# CAN_connectors.net
KiCad netlist of a schematic drawn in Altium Designer
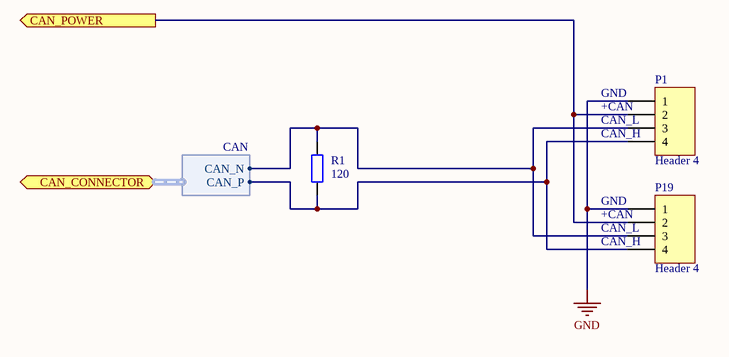
[diagram p0: CAN connectors.SchDoc]

(export (version "E")
  (design (tool "Eeschema 10.0.6"))
  (components
    (comp (ref "P1")
      (value "Header 4")
      (footprint "B04B-PASK-1")
      (description "Header, 4-Pin")
      (fields (field (name "PUBLISHER") "Altium Limited"))
      (libsource (lib "Miscellaneous Connectors") (part "Header 4"))
    )
    (comp (ref "P19")
      (value "Header 4")
      (footprint "B04B-PASK-1")
      (description "Header, 4-Pin")
      (fields (field (name "PUBLISHER") "Altium Limited"))
      (libsource (lib "Miscellaneous Connectors") (part "Header 4"))
    )
    (comp (ref "R1")
      (value "120")
      (footprint "R0603")
      (description "Resistor")
      (fields (field (name "Comment") "Res2") (field (name "PUBLISHER") "Altium Limited"))
      (libsource (lib "Miscellaneous Devices") (part "Res2"))
    )
  )
  (nets
    (net (code "2") (name "/CAN_POWER") (class "Default")
      (node (ref "P1") (pin "2") (pinfunction "2_2") (pintype "passive"))
      (node (ref "P19") (pin "2") (pinfunction "2_2") (pintype "passive"))
    )
    (net (code "4") (name "GND") (class "Default")
      (node (ref "P1") (pin "1") (pinfunction "1_1") (pintype "passive"))
      (node (ref "P19") (pin "1") (pinfunction "1_1") (pintype "passive"))
    )
    (net (code "5") (name "Net-(P1-Pad3)") (class "Default")
      (node (ref "P1") (pin "3") (pinfunction "3_3") (pintype "passive"))
      (node (ref "P19") (pin "3") (pinfunction "3_3") (pintype "passive"))
      (node (ref "R1") (pin "2") (pinfunction "2_2") (pintype "passive"))
    )
    (net (code "6") (name "Net-(P1-Pad4)") (class "Default")
      (node (ref "P1") (pin "4") (pinfunction "4_4") (pintype "passive"))
      (node (ref "P19") (pin "4") (pinfunction "4_4") (pintype "passive"))
      (node (ref "R1") (pin "1") (pinfunction "1_1") (pintype "passive"))
    )
  )
)
